# MBus-ESP-01.net
KiCad netlist of a schematic drawn in EAGLE
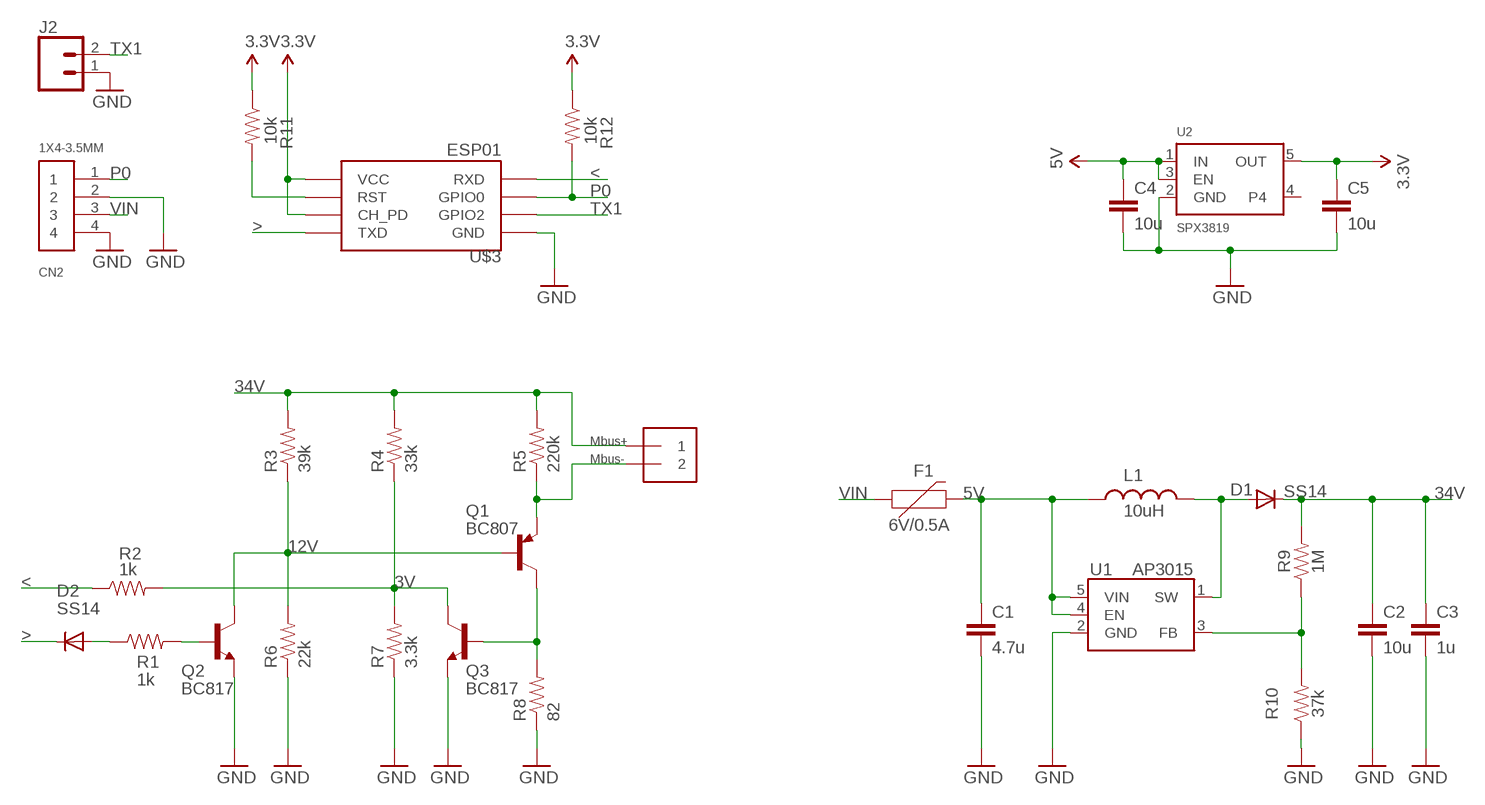
[diagram p0: schematic, sheet 1]

(export (version "E")
  (design (tool "Eeschema 10.0.6"))
  (components
    (comp (ref "C1")
      (value "4.7u")
      (footprint "eagle-import:0805")
      (libsource (lib "eagle-import") (part "1.0UF-0805-25V-(+80/-20%)"))
    )
    (comp (ref "C2")
      (value "10u")
      (footprint "eagle-import:1206")
      (libsource (lib "eagle-import") (part "1.0UF-1206-50V-10%"))
    )
    (comp (ref "C3")
      (value "1u")
      (footprint "eagle-import:1206")
      (libsource (lib "eagle-import") (part "1.0UF-1206-50V-10%"))
    )
    (comp (ref "C4")
      (value "10u")
      (footprint "eagle-import:0603-CAP")
      (libsource (lib "eagle-import") (part "CAP0603-CAP"))
    )
    (comp (ref "C5")
      (value "10u")
      (footprint "eagle-import:0603-CAP")
      (libsource (lib "eagle-import") (part "CAP0603-CAP"))
    )
    (comp (ref "CN2")
      (value "1X4-3.5MM")
      (footprint "eagle-import:1X04-3.5MM")
      (libsource (lib "eagle-import") (part "1X4-3.5MM"))
    )
    (comp (ref "D1")
      (value "SS14")
      (footprint "eagle-import:SOD-123")
      (libsource (lib "eagle-import") (part "DIODESOD-123"))
    )
    (comp (ref "D2")
      (value "SS14")
      (footprint "eagle-import:SOD-123")
      (libsource (lib "eagle-import") (part "DIODESOD-123"))
    )
    (comp (ref "F1")
      (value "6V/0.5A")
      (footprint "eagle-import:1206")
      (libsource (lib "eagle-import") (part "PPTC_HALF-AMP"))
    )
    (comp (ref "J1")
      (value "1X2-3.5MM")
      (footprint "eagle-import:1X2-3.5MM")
      (libsource (lib "eagle-import") (part "1X2-3.5MM"))
    )
    (comp (ref "J2")
      (value "CONN_021X02_NO_SILK")
      (footprint "eagle-import:1X02_NO_SILK")
      (libsource (lib "eagle-import") (part "CONN_021X02_NO_SILK"))
    )
    (comp (ref "L1")
      (value "10uH")
      (footprint "eagle-import:B82462G")
      (libsource (lib "eagle-import") (part "INDUCTOR-B82462G"))
    )
    (comp (ref "Q1")
      (value "BC807")
      (footprint "eagle-import:SOT23-BEC")
      (libsource (lib "eagle-import") (part "-PNP-SOT23-BECBC807-16"))
    )
    (comp (ref "Q2")
      (value "BC817")
      (footprint "eagle-import:SOT23-BEC")
      (libsource (lib "eagle-import") (part "BC817SMD-16"))
    )
    (comp (ref "Q3")
      (value "BC817")
      (footprint "eagle-import:SOT23-BEC")
      (libsource (lib "eagle-import") (part "BC817SMD-16"))
    )
    (comp (ref "R1")
      (value "1k")
      (footprint "eagle-import:0805")
      (libsource (lib "eagle-import") (part "RESISTOR0805"))
    )
    (comp (ref "R2")
      (value "1k")
      (footprint "eagle-import:0805")
      (libsource (lib "eagle-import") (part "RESISTOR0805"))
    )
    (comp (ref "R3")
      (value "39k")
      (footprint "eagle-import:0805")
      (libsource (lib "eagle-import") (part "RESISTOR0805"))
    )
    (comp (ref "R4")
      (value "33k")
      (footprint "eagle-import:0805")
      (libsource (lib "eagle-import") (part "RESISTOR0805"))
    )
    (comp (ref "R5")
      (value "220k")
      (footprint "eagle-import:1206")
      (libsource (lib "eagle-import") (part "RESISTOR1206"))
    )
    (comp (ref "R6")
      (value "22k")
      (footprint "eagle-import:0805")
      (libsource (lib "eagle-import") (part "RESISTOR0805"))
    )
    (comp (ref "R7")
      (value "3.3k")
      (footprint "eagle-import:0805")
      (libsource (lib "eagle-import") (part "RESISTOR0805"))
    )
    (comp (ref "R8")
      (value "82")
      (footprint "eagle-import:1206")
      (libsource (lib "eagle-import") (part "RESISTOR1206"))
    )
    (comp (ref "R9")
      (value "1M")
      (footprint "eagle-import:0805")
      (libsource (lib "eagle-import") (part "RESISTOR0805"))
    )
    (comp (ref "R10")
      (value "37k")
      (footprint "eagle-import:0805")
      (libsource (lib "eagle-import") (part "RESISTOR0805"))
    )
    (comp (ref "R11")
      (value "10k")
      (footprint "eagle-import:0805")
      (libsource (lib "eagle-import") (part "RESISTOR0805"))
    )
    (comp (ref "R12")
      (value "10k")
      (footprint "eagle-import:0805")
      (libsource (lib "eagle-import") (part "RESISTOR0805"))
    )
    (comp (ref "U$3")
      (value "ESP01")
      (footprint "eagle-import:ESP01")
      (libsource (lib "eagle-import") (part "ESP01"))
    )
    (comp (ref "U1")
      (value "AP3015")
      (footprint "eagle-import:SOT-23-5")
      (libsource (lib "eagle-import") (part "AP3015"))
    )
    (comp (ref "U2")
      (value "SPX3819")
      (footprint "eagle-import:SOT23-5")
      (libsource (lib "eagle-import") (part "VREG_SOT23-5"))
    )
  )
  (nets
    (net (code "1") (name "/3V") (class "Default")
      (node (ref "Q3") (pin "C") (pinfunction "C_C") (pintype "passive"))
      (node (ref "R2") (pin "2") (pinfunction "2_2") (pintype "passive"))
      (node (ref "R4") (pin "1") (pinfunction "1_1") (pintype "passive"))
      (node (ref "R7") (pin "2") (pinfunction "2_2") (pintype "passive"))
    )
    (net (code "2") (name "/12V") (class "Default")
      (node (ref "Q1") (pin "B") (pinfunction "B_B") (pintype "passive"))
      (node (ref "Q2") (pin "C") (pinfunction "C_C") (pintype "passive"))
      (node (ref "R3") (pin "1") (pinfunction "1_1") (pintype "passive"))
      (node (ref "R6") (pin "2") (pinfunction "2_2") (pintype "passive"))
    )
    (net (code "3") (name "/34V") (class "Default")
      (node (ref "C2") (pin "1") (pinfunction "1_1") (pintype "passive"))
      (node (ref "C3") (pin "1") (pinfunction "1_1") (pintype "passive"))
      (node (ref "D1") (pin "C") (pinfunction "C_C") (pintype "passive"))
      (node (ref "J1") (pin "1") (pinfunction "1_1") (pintype "passive"))
      (node (ref "R3") (pin "2") (pinfunction "2_2") (pintype "passive"))
      (node (ref "R4") (pin "2") (pinfunction "2_2") (pintype "passive"))
      (node (ref "R5") (pin "2") (pinfunction "2_2") (pintype "passive"))
      (node (ref "R9") (pin "2") (pinfunction "2_2") (pintype "passive"))
    )
    (net (code "4") (name "/<") (class "Default")
      (node (ref "R2") (pin "1") (pinfunction "1_1") (pintype "passive"))
      (node (ref "U$3") (pin "RX") (pinfunction "RXD_RX") (pintype "bidirectional"))
    )
    (net (code "5") (name "/>") (class "Default")
      (node (ref "D2") (pin "C") (pinfunction "C_C") (pintype "passive"))
      (node (ref "U$3") (pin "TX") (pinfunction "TXD_TX") (pintype "bidirectional"))
    )
    (net (code "6") (name "/P0") (class "Default")
      (node (ref "CN2") (pin "1") (pinfunction "1_1") (pintype "bidirectional"))
      (node (ref "R12") (pin "2") (pinfunction "2_2") (pintype "passive"))
      (node (ref "U$3") (pin "GPIO0") (pinfunction "GPIO0_GPIO0") (pintype "bidirectional"))
    )
    (net (code "7") (name "/TX1") (class "Default")
      (node (ref "J2") (pin "2") (pinfunction "2_2") (pintype "passive"))
      (node (ref "U$3") (pin "GPIO2") (pinfunction "GPIO2_GPIO2") (pintype "bidirectional"))
    )
    (net (code "8") (name "/VIN") (class "Default")
      (node (ref "CN2") (pin "3") (pinfunction "3_3") (pintype "bidirectional"))
      (node (ref "F1") (pin "1") (pinfunction "1_1") (pintype "bidirectional"))
    )
    (net (code "9") (name "3.3V") (class "Default")
      (node (ref "C5") (pin "1") (pinfunction "1_1") (pintype "passive"))
      (node (ref "R11") (pin "1") (pinfunction "1_1") (pintype "passive"))
      (node (ref "R12") (pin "1") (pinfunction "1_1") (pintype "passive"))
      (node (ref "U$3") (pin "CH_PD") (pinfunction "CH_PD_CH_PD") (pintype "bidirectional"))
      (node (ref "U$3") (pin "VCC") (pinfunction "VCC_VCC") (pintype "bidirectional"))
      (node (ref "U2") (pin "5") (pinfunction "OUT_5") (pintype "power_in"))
    )
    (net (code "10") (name "5V") (class "Default")
      (node (ref "C1") (pin "1") (pinfunction "1_1") (pintype "passive"))
      (node (ref "C4") (pin "1") (pinfunction "1_1") (pintype "passive"))
      (node (ref "F1") (pin "2") (pinfunction "2_2") (pintype "bidirectional"))
      (node (ref "L1") (pin "P$1") (pinfunction "1_P$1") (pintype "passive"))
      (node (ref "U1") (pin "4") (pinfunction "EN_4") (pintype "input"))
      (node (ref "U1") (pin "5") (pinfunction "VIN_5") (pintype "power_in"))
      (node (ref "U2") (pin "1") (pinfunction "IN_1") (pintype "power_in"))
      (node (ref "U2") (pin "3") (pinfunction "EN_3") (pintype "input"))
    )
    (net (code "11") (name "GND") (class "Default")
      (node (ref "C1") (pin "2") (pinfunction "2_2") (pintype "passive"))
      (node (ref "C2") (pin "2") (pinfunction "2_2") (pintype "passive"))
      (node (ref "C3") (pin "2") (pinfunction "2_2") (pintype "passive"))
      (node (ref "C4") (pin "2") (pinfunction "2_2") (pintype "passive"))
      (node (ref "C5") (pin "2") (pinfunction "2_2") (pintype "passive"))
      (node (ref "CN2") (pin "2") (pinfunction "2_2") (pintype "bidirectional"))
      (node (ref "CN2") (pin "4") (pinfunction "4_4") (pintype "bidirectional"))
      (node (ref "J2") (pin "1") (pinfunction "1_1") (pintype "passive"))
      (node (ref "Q2") (pin "E") (pinfunction "E_E") (pintype "passive"))
      (node (ref "Q3") (pin "E") (pinfunction "E_E") (pintype "passive"))
      (node (ref "R10") (pin "1") (pinfunction "1_1") (pintype "passive"))
      (node (ref "R6") (pin "1") (pinfunction "1_1") (pintype "passive"))
      (node (ref "R7") (pin "1") (pinfunction "1_1") (pintype "passive"))
      (node (ref "R8") (pin "1") (pinfunction "1_1") (pintype "passive"))
      (node (ref "U$3") (pin "GND") (pinfunction "GND_GND") (pintype "bidirectional"))
      (node (ref "U1") (pin "2") (pinfunction "GND_2") (pintype "power_in"))
      (node (ref "U2") (pin "2") (pinfunction "GND_2") (pintype "power_in"))
    )
    (net (code "12") (name "Net-(D2-PadA)") (class "Default")
      (node (ref "D2") (pin "A") (pinfunction "A_A") (pintype "passive"))
      (node (ref "R1") (pin "1") (pinfunction "1_1") (pintype "passive"))
    )
    (net (code "13") (name "Net-(J1-Pad2)") (class "Default")
      (node (ref "J1") (pin "2") (pinfunction "2_2") (pintype "passive"))
      (node (ref "Q1") (pin "E") (pinfunction "E_E") (pintype "passive"))
      (node (ref "R5") (pin "1") (pinfunction "1_1") (pintype "passive"))
    )
    (net (code "14") (name "Net-(L1-2)") (class "Default")
      (node (ref "D1") (pin "A") (pinfunction "A_A") (pintype "passive"))
      (node (ref "L1") (pin "P$2") (pinfunction "2_P$2") (pintype "passive"))
      (node (ref "U1") (pin "1") (pinfunction "SW_1") (pintype "output"))
    )
    (net (code "15") (name "Net-(Q1-PadC)") (class "Default")
      (node (ref "Q1") (pin "C") (pinfunction "C_C") (pintype "passive"))
      (node (ref "Q3") (pin "B") (pinfunction "B_B") (pintype "passive"))
      (node (ref "R8") (pin "2") (pinfunction "2_2") (pintype "passive"))
    )
    (net (code "16") (name "Net-(Q2-PadB)") (class "Default")
      (node (ref "Q2") (pin "B") (pinfunction "B_B") (pintype "passive"))
      (node (ref "R1") (pin "2") (pinfunction "2_2") (pintype "passive"))
    )
    (net (code "17") (name "Net-(R11-Pad2)") (class "Default")
      (node (ref "R11") (pin "2") (pinfunction "2_2") (pintype "passive"))
      (node (ref "U$3") (pin "RST") (pinfunction "RST_RST") (pintype "bidirectional"))
    )
    (net (code "18") (name "Net-(U1-FB)") (class "Default")
      (node (ref "R10") (pin "2") (pinfunction "2_2") (pintype "passive"))
      (node (ref "R9") (pin "1") (pinfunction "1_1") (pintype "passive"))
      (node (ref "U1") (pin "3") (pinfunction "FB_3") (pintype "input"))
    )
    (net (code "19") (name "unconnected-(U2-P4-Pad4)") (class "Default")
      (node (ref "U2") (pin "4") (pinfunction "P4_4") (pintype "bidirectional"))
    )
  )
)
